# scematic.net
KiCad netlist of a schematic drawn in Altium Designer
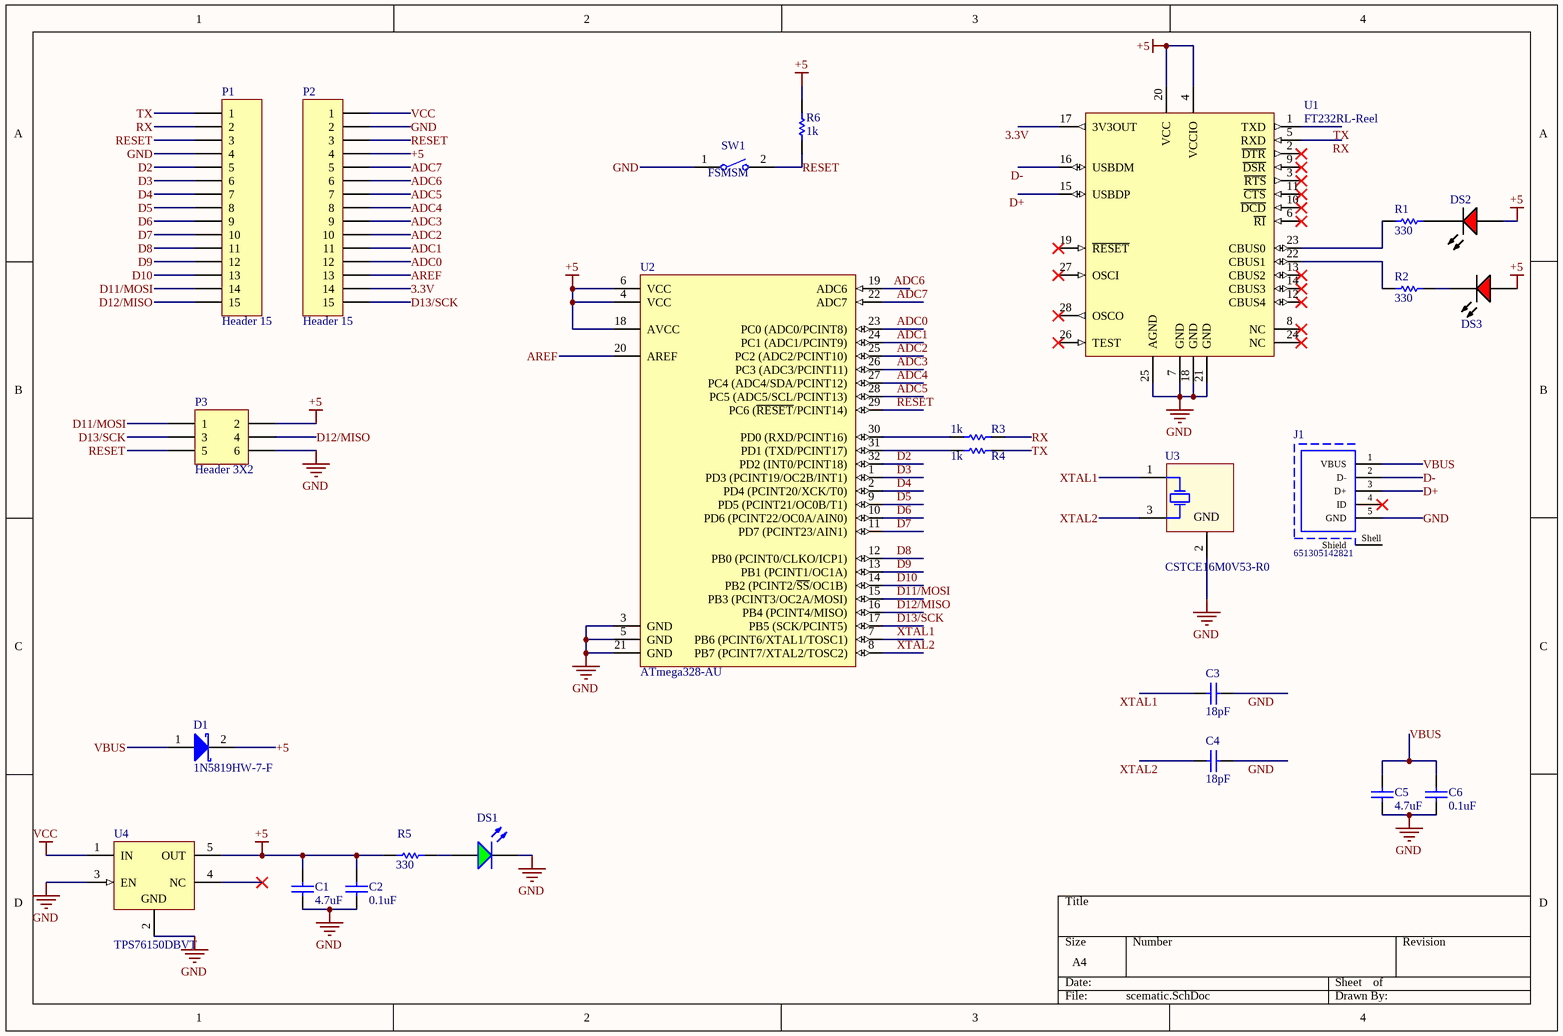
[diagram p0: scematic.SchDoc]

(export (version "E")
  (design (tool "Eeschema 10.0.6"))
  (components
    (comp (ref "C1")
      (value "4.7uF")
      (footprint "CAPC1005X55X25NL05T10")
      (fields (field (name "PART NUMBER") "GRM155R60J475ME47D") (field (name "MANUFACTURER") "Murata"))
      (libsource (lib "Altium Content Vault") (part "CAP"))
    )
    (comp (ref "C2")
      (value "0.1uF")
      (footprint "CAPC1005X55X25ML05T10")
      (description "Chip Capacitor, 0.1 uF, +/- 10%, 16 V, -55 to 125 degC, 0402 (1005 Metric), RoHS, Tape and Reel")
      (fields (field (name "VOLTAGE") "16V") (field (name "TOLERANCE") "10%"))
      (libsource (lib "Altium Content Vault") (part "CAP-NP-2"))
    )
    (comp (ref "C3")
      (value "18pF")
      (footprint "CAPC1005X55X30LL05T10")
      (fields (field (name "PART NUMBER") "C0402C180J5GACTU") (field (name "MANUFACTURER") "Kemet"))
      (libsource (lib "Altium Content Vault") (part "CAP"))
    )
    (comp (ref "C4")
      (value "18pF")
      (footprint "CAPC1005X55X30LL05T10")
      (fields (field (name "PART NUMBER") "C0402C180J5GACTU") (field (name "MANUFACTURER") "Kemet"))
      (libsource (lib "Altium Content Vault") (part "CAP"))
    )
    (comp (ref "C5")
      (value "4.7uF")
      (footprint "CAPC1005X55X25NL05T10")
      (fields (field (name "PART NUMBER") "GRM155R60J475ME47D") (field (name "MANUFACTURER") "Murata"))
      (libsource (lib "Altium Content Vault") (part "CAP"))
    )
    (comp (ref "C6")
      (value "0.1uF")
      (footprint "CAPC1005X55X25ML05T10")
      (description "Chip Capacitor, 0.1 uF, +/- 10%, 16 V, -55 to 125 degC, 0402 (1005 Metric), RoHS, Tape and Reel")
      (fields (field (name "VOLTAGE") "16V") (field (name "TOLERANCE") "10%"))
      (libsource (lib "Altium Content Vault") (part "CAP-NP-2"))
    )
    (comp (ref "D1")
      (value "1N5819HW-7-F")
      (footprint "DIOD-SOD-123-2_V")
      (fields (field (name "MANUFACTURER") "Diodes Inc"))
      (libsource (lib "Altium Content Vault") (part "DIOD-DSKY-A1K2-2"))
    )
    (comp (ref "DS1")
      (value "APT1608SGC")
      (footprint "KING-APT1608SGC_V")
      (description "Super Bright Green LED, 62.5 mW, 25 mA, -40 to 85 degC, 2-Pin SMD, RoHS, Tape and Reel")
      (fields (field (name "MANUFACTURER") "Kingbright"))
      (libsource (lib "Altium Content Vault") (part "LED-GREEN-AK-2"))
    )
    (comp (ref "DS2")
      (value "TLMS1000-GS08")
      (footprint "VISH-TLMS1000_V")
      (description "Low Current LED, 40 mW, 1.8 V, -40 to 100 degC, 2-Pin SMD (0603), RoHS, Tape and Reel")
      (fields (field (name "MANUFACTURER") "Vishay"))
      (libsource (lib "Altium Content Vault") (part "LED-RED-AK-2"))
    )
    (comp (ref "DS3")
      (value "TLMS1000-GS08")
      (footprint "VISH-TLMS1000_V")
      (description "Low Current LED, 40 mW, 1.8 V, -40 to 100 degC, 2-Pin SMD (0603), RoHS, Tape and Reel")
      (fields (field (name "MANUFACTURER") "Vishay"))
      (libsource (lib "Altium Content Vault") (part "LED-RED-AK-2"))
    )
    (comp (ref "J1")
      (value "651305142821")
      (footprint "651305142821")
      (description "Mini USB 2.0 Type AB Receptacle WR-COM, Horizontal, SMT, with Pads")
      (fields (field (name "MANUFACTURER") "Wurth Elektronik") (field (name "PUBLISHER") "WurthElektronik"))
      (libsource (lib "Altium Content Vault") (part "WE-USB-5-1SHLD"))
    )
    (comp (ref "P1")
      (value "Header 15")
      (footprint "HDR1X15")
      (description "Header, 15-Pin")
      (fields (field (name "PUBLISHER") "Altium Limited"))
      (libsource (lib "") (part "Header 15_1"))
    )
    (comp (ref "P2")
      (value "Header 15")
      (footprint "HDR1X15")
      (description "Header, 15-Pin")
      (fields (field (name "PUBLISHER") "Altium Limited"))
      (libsource (lib "Miscellaneous Connectors") (part "Header 15"))
    )
    (comp (ref "P3")
      (value "Header 3X2")
      (footprint "HDR2X3")
      (description "Header, 3-Pin, Dual row")
      (fields (field (name "PUBLISHER") "Altium Limited"))
      (libsource (lib "Miscellaneous Connectors") (part "Header 3X2"))
    )
    (comp (ref "R1")
      (value "330")
      (footprint "RESC1608X55X30ML15T15")
      (fields (field (name "PART NUMBER") "ERJ-3GEYJ331V") (field (name "MANUFACTURER") "Panasonic"))
      (libsource (lib "Altium Content Vault") (part "RES"))
    )
    (comp (ref "R2")
      (value "330")
      (footprint "RESC1608X55X30ML15T15")
      (fields (field (name "PART NUMBER") "ERJ-3GEYJ331V") (field (name "MANUFACTURER") "Panasonic"))
      (libsource (lib "Altium Content Vault") (part "RES"))
    )
    (comp (ref "R3")
      (value "1k")
      (footprint "RESC1608X55X30ML15T15")
      (fields (field (name "PART NUMBER") "ERJ-3GEYJ331V") (field (name "MANUFACTURER") "Panasonic"))
      (libsource (lib "Altium Content Vault") (part "RES"))
    )
    (comp (ref "R4")
      (value "1k")
      (footprint "RESC1608X55X30ML15T15")
      (fields (field (name "PART NUMBER") "ERJ-3GEYJ331V") (field (name "MANUFACTURER") "Panasonic"))
      (libsource (lib "Altium Content Vault") (part "RES"))
    )
    (comp (ref "R5")
      (value "330")
      (footprint "RESC1608X55X30ML15T15")
      (fields (field (name "PART NUMBER") "ERJ-3GEYJ331V") (field (name "MANUFACTURER") "Panasonic"))
      (libsource (lib "Altium Content Vault") (part "RES"))
    )
    (comp (ref "R6")
      (value "1k")
      (footprint "RESC1608X55X30ML15T15")
      (fields (field (name "PART NUMBER") "ERJ-3GEYJ331V") (field (name "MANUFACTURER") "Panasonic"))
      (libsource (lib "Altium Content Vault") (part "RES"))
    )
    (comp (ref "SW1")
      (value "FSMSM")
      (footprint "TECO-FSMSM-2_V")
      (description "FSMSM Push Button Switch, 50 mA, -35 to 85 degC, 2-Pin SMD, RoHS, Bulk")
      (fields (field (name "MANUFACTURER") "TE Connectivity"))
      (libsource (lib "Altium Content Vault") (part "SW-SPST-2_C"))
    )
    (comp (ref "U1")
      (value "FT232RL-Reel")
      (footprint "SSOP-28_L")
      (description "USB UART Asynchronous Serial Data Transfer Chip, 28-pin SSOP, Tape and Reel")
      (fields (field (name "MANUFACTURER") "FTDI"))
      (libsource (lib "Altium Content Vault") (part "COM-UART-FT232R-IL28"))
    )
    (comp (ref "U2")
      (value "ATmega328-AU")
      (footprint "32A_L")
      (libsource (lib "Altium Content Vault") (part "MC-8B-ATM48-SQ32"))
    )
    (comp (ref "U3")
      (value "CSTCE16M0V53-R0")
      (footprint "MURA-CSTCE_V-3_V")
      (fields (field (name "MANUFACTURER") "Murata"))
      (libsource (lib "Altium Content Vault") (part "MURA-CSTCE_V-3"))
    )
    (comp (ref "U4")
      (value "TPS76150DBVT")
      (footprint "DBV0005A_N")
      (fields (field (name "MANUFACTURER") "Texas Instruments"))
      (libsource (lib "Altium Content Vault") (part "TI-TXX7XXXX-5"))
    )
  )
  (nets
    (net (code "1") (name "+5") (class "Default")
      (node (ref "C1") (pin "2") (pinfunction "2_2") (pintype "passive"))
      (node (ref "C2") (pin "2") (pinfunction "2_2") (pintype "passive"))
      (node (ref "D1") (pin "2") (pinfunction "K_2") (pintype "passive"))
      (node (ref "DS2") (pin "1") (pinfunction "A_1") (pintype "passive"))
      (node (ref "DS3") (pin "1") (pinfunction "A_1") (pintype "passive"))
      (node (ref "P2") (pin "4") (pinfunction "4_4") (pintype "passive"))
      (node (ref "P3") (pin "2") (pinfunction "2_2") (pintype "passive"))
      (node (ref "R5") (pin "1") (pinfunction "1_1") (pintype "passive"))
      (node (ref "R6") (pin "2") (pinfunction "2_2") (pintype "passive"))
      (node (ref "U1") (pin "20") (pinfunction "VCC_20") (pintype "power_in"))
      (node (ref "U1") (pin "4") (pinfunction "VCCIO_4") (pintype "power_in"))
      (node (ref "U2") (pin "18") (pinfunction "AVCC_18") (pintype "power_in"))
      (node (ref "U2") (pin "4") (pinfunction "VCC_4") (pintype "power_in"))
      (node (ref "U2") (pin "6") (pinfunction "VCC_6") (pintype "power_in"))
      (node (ref "U4") (pin "5") (pinfunction "OUT_5") (pintype "power_in"))
    )
    (net (code "2") (name "/3.3V") (class "Default")
      (node (ref "P2") (pin "14") (pinfunction "14_14") (pintype "passive"))
      (node (ref "U1") (pin "17") (pinfunction "3V3OUT_17") (pintype "output"))
    )
    (net (code "3") (name "/ADC0") (class "Default")
      (node (ref "P2") (pin "12") (pinfunction "12_12") (pintype "passive"))
      (node (ref "U2") (pin "23") (pinfunction "PC0_(ADC0/PCINT8)_23") (pintype "bidirectional"))
    )
    (net (code "4") (name "/ADC1") (class "Default")
      (node (ref "P2") (pin "11") (pinfunction "11_11") (pintype "passive"))
      (node (ref "U2") (pin "24") (pinfunction "PC1_(ADC1/PCINT9)_24") (pintype "bidirectional"))
    )
    (net (code "5") (name "/ADC2") (class "Default")
      (node (ref "P2") (pin "10") (pinfunction "10_10") (pintype "passive"))
      (node (ref "U2") (pin "25") (pinfunction "PC2_(ADC2/PCINT10)_25") (pintype "bidirectional"))
    )
    (net (code "6") (name "/ADC3") (class "Default")
      (node (ref "P2") (pin "9") (pinfunction "9_9") (pintype "passive"))
      (node (ref "U2") (pin "26") (pinfunction "PC3_(ADC3/PCINT11)_26") (pintype "bidirectional"))
    )
    (net (code "7") (name "/ADC4") (class "Default")
      (node (ref "P2") (pin "8") (pinfunction "8_8") (pintype "passive"))
      (node (ref "U2") (pin "27") (pinfunction "PC4_(ADC4/SDA/PCINT12)_27") (pintype "bidirectional"))
    )
    (net (code "8") (name "/ADC5") (class "Default")
      (node (ref "P2") (pin "7") (pinfunction "7_7") (pintype "passive"))
      (node (ref "U2") (pin "28") (pinfunction "PC5_(ADC5/SCL/PCINT13)_28") (pintype "bidirectional"))
    )
    (net (code "9") (name "/ADC6") (class "Default")
      (node (ref "P2") (pin "6") (pinfunction "6_6") (pintype "passive"))
      (node (ref "U2") (pin "19") (pinfunction "ADC6_19") (pintype "input"))
    )
    (net (code "10") (name "/ADC7") (class "Default")
      (node (ref "P2") (pin "5") (pinfunction "5_5") (pintype "passive"))
      (node (ref "U2") (pin "22") (pinfunction "ADC7_22") (pintype "input"))
    )
    (net (code "11") (name "/AREF") (class "Default")
      (node (ref "P2") (pin "13") (pinfunction "13_13") (pintype "passive"))
      (node (ref "U2") (pin "20") (pinfunction "AREF_20") (pintype "passive"))
    )
    (net (code "12") (name "/D+") (class "Default")
      (node (ref "J1") (pin "3") (pinfunction "D+_3") (pintype "passive"))
      (node (ref "U1") (pin "15") (pinfunction "USBDP_15") (pintype "bidirectional"))
    )
    (net (code "13") (name "/D-") (class "Default")
      (node (ref "J1") (pin "2") (pinfunction "D-_2") (pintype "passive"))
      (node (ref "U1") (pin "16") (pinfunction "USBDM_16") (pintype "bidirectional"))
    )
    (net (code "14") (name "/D2") (class "Default")
      (node (ref "P1") (pin "5") (pinfunction "5_5") (pintype "passive"))
      (node (ref "U2") (pin "32") (pinfunction "PD2_(INT0/PCINT18)_32") (pintype "bidirectional"))
    )
    (net (code "15") (name "/D3") (class "Default")
      (node (ref "P1") (pin "6") (pinfunction "6_6") (pintype "passive"))
      (node (ref "U2") (pin "1") (pinfunction "PD3_(PCINT19/OC2B/INT1)_1") (pintype "bidirectional"))
    )
    (net (code "16") (name "/D4") (class "Default")
      (node (ref "P1") (pin "7") (pinfunction "7_7") (pintype "passive"))
      (node (ref "U2") (pin "2") (pinfunction "PD4_(PCINT20/XCK/T0)_2") (pintype "bidirectional"))
    )
    (net (code "17") (name "/D5") (class "Default")
      (node (ref "P1") (pin "8") (pinfunction "8_8") (pintype "passive"))
      (node (ref "U2") (pin "9") (pinfunction "PD5_(PCINT21/OC0B/T1)_9") (pintype "bidirectional"))
    )
    (net (code "18") (name "/D6") (class "Default")
      (node (ref "P1") (pin "9") (pinfunction "9_9") (pintype "passive"))
      (node (ref "U2") (pin "10") (pinfunction "PD6_(PCINT22/OC0A/AIN0)_10") (pintype "bidirectional"))
    )
    (net (code "19") (name "/D7") (class "Default")
      (node (ref "P1") (pin "10") (pinfunction "10_10") (pintype "passive"))
      (node (ref "U2") (pin "11") (pinfunction "PD7_(PCINT23/AIN1)_11") (pintype "bidirectional"))
    )
    (net (code "20") (name "/D8") (class "Default")
      (node (ref "P1") (pin "11") (pinfunction "11_11") (pintype "passive"))
      (node (ref "U2") (pin "12") (pinfunction "PB0_(PCINT0/CLKO/ICP1)_12") (pintype "bidirectional"))
    )
    (net (code "21") (name "/D9") (class "Default")
      (node (ref "P1") (pin "12") (pinfunction "12_12") (pintype "passive"))
      (node (ref "U2") (pin "13") (pinfunction "PB1_(PCINT1/OC1A)_13") (pintype "bidirectional"))
    )
    (net (code "22") (name "/D10") (class "Default")
      (node (ref "P1") (pin "13") (pinfunction "13_13") (pintype "passive"))
      (node (ref "U2") (pin "14") (pinfunction "PB2_(PCINT2/~{SS}/OC1B)_14") (pintype "bidirectional"))
    )
    (net (code "23") (name "/D11{slash}MOSI") (class "Default")
      (node (ref "P1") (pin "14") (pinfunction "14_14") (pintype "passive"))
      (node (ref "P3") (pin "1") (pinfunction "1_1") (pintype "passive"))
      (node (ref "U2") (pin "15") (pinfunction "PB3_(PCINT3/OC2A/MOSI)_15") (pintype "bidirectional"))
    )
    (net (code "24") (name "/D12{slash}MISO") (class "Default")
      (node (ref "P1") (pin "15") (pinfunction "15_15") (pintype "passive"))
      (node (ref "P3") (pin "4") (pinfunction "4_4") (pintype "passive"))
      (node (ref "U2") (pin "16") (pinfunction "PB4_(PCINT4/MISO)_16") (pintype "bidirectional"))
    )
    (net (code "25") (name "/D13{slash}SCK") (class "Default")
      (node (ref "P2") (pin "15") (pinfunction "15_15") (pintype "passive"))
      (node (ref "P3") (pin "3") (pinfunction "3_3") (pintype "passive"))
      (node (ref "U2") (pin "17") (pinfunction "PB5_(SCK/PCINT5)_17") (pintype "bidirectional"))
    )
    (net (code "26") (name "/RESET") (class "Default")
      (node (ref "P1") (pin "3") (pinfunction "3_3") (pintype "passive"))
      (node (ref "P2") (pin "3") (pinfunction "3_3") (pintype "passive"))
      (node (ref "P3") (pin "5") (pinfunction "5_5") (pintype "passive"))
      (node (ref "R6") (pin "1") (pinfunction "1_1") (pintype "passive"))
      (node (ref "SW1") (pin "2") (pinfunction "2_2") (pintype "passive"))
      (node (ref "U2") (pin "29") (pinfunction "PC6_(~{RESET}/PCINT14)_29") (pintype "bidirectional"))
    )
    (net (code "27") (name "/RX") (class "Default")
      (node (ref "P1") (pin "2") (pinfunction "2_2") (pintype "passive"))
      (node (ref "R3") (pin "2") (pinfunction "2_2") (pintype "passive"))
      (node (ref "U1") (pin "5") (pinfunction "RXD_5") (pintype "input"))
    )
    (net (code "28") (name "/TX") (class "Default")
      (node (ref "P1") (pin "1") (pinfunction "1_1") (pintype "passive"))
      (node (ref "R4") (pin "2") (pinfunction "2_2") (pintype "passive"))
      (node (ref "U1") (pin "1") (pinfunction "TXD_1") (pintype "output"))
    )
    (net (code "29") (name "/VBUS") (class "Default")
      (node (ref "C5") (pin "2") (pinfunction "2_2") (pintype "passive"))
      (node (ref "C6") (pin "2") (pinfunction "2_2") (pintype "passive"))
      (node (ref "D1") (pin "1") (pinfunction "A_1") (pintype "passive"))
      (node (ref "J1") (pin "1") (pinfunction "VBUS_1") (pintype "passive"))
    )
    (net (code "30") (name "/XTAL1") (class "Default")
      (node (ref "C3") (pin "1") (pinfunction "1_1") (pintype "passive"))
      (node (ref "U2") (pin "7") (pinfunction "PB6_(PCINT6/XTAL1/TOSC1)_7") (pintype "bidirectional"))
      (node (ref "U3") (pin "1") (pinfunction "C1_1") (pintype "passive"))
    )
    (net (code "31") (name "/XTAL2") (class "Default")
      (node (ref "C4") (pin "1") (pinfunction "1_1") (pintype "passive"))
      (node (ref "U2") (pin "8") (pinfunction "PB7_(PCINT7/XTAL2/TOSC2)_8") (pintype "bidirectional"))
      (node (ref "U3") (pin "3") (pinfunction "C2_3") (pintype "passive"))
    )
    (net (code "32") (name "GND") (class "Default")
      (node (ref "C1") (pin "1") (pinfunction "1_1") (pintype "passive"))
      (node (ref "C2") (pin "1") (pinfunction "1_1") (pintype "passive"))
      (node (ref "C3") (pin "2") (pinfunction "2_2") (pintype "passive"))
      (node (ref "C4") (pin "2") (pinfunction "2_2") (pintype "passive"))
      (node (ref "C5") (pin "1") (pinfunction "1_1") (pintype "passive"))
      (node (ref "C6") (pin "1") (pinfunction "1_1") (pintype "passive"))
      (node (ref "DS1") (pin "2") (pinfunction "K_2") (pintype "passive"))
      (node (ref "J1") (pin "5") (pinfunction "GND_5") (pintype "passive"))
      (node (ref "P1") (pin "4") (pinfunction "4_4") (pintype "passive"))
      (node (ref "P2") (pin "2") (pinfunction "2_2") (pintype "passive"))
      (node (ref "P3") (pin "6") (pinfunction "6_6") (pintype "passive"))
      (node (ref "SW1") (pin "1") (pinfunction "1_1") (pintype "passive"))
      (node (ref "U1") (pin "18") (pinfunction "GND_18") (pintype "power_in"))
      (node (ref "U1") (pin "21") (pinfunction "GND_21") (pintype "power_in"))
      (node (ref "U1") (pin "25") (pinfunction "AGND_25") (pintype "power_in"))
      (node (ref "U1") (pin "7") (pinfunction "GND_7") (pintype "power_in"))
      (node (ref "U2") (pin "21") (pinfunction "GND_21") (pintype "power_in"))
      (node (ref "U2") (pin "3") (pinfunction "GND_3") (pintype "power_in"))
      (node (ref "U2") (pin "5") (pinfunction "GND_5") (pintype "power_in"))
      (node (ref "U3") (pin "2") (pinfunction "GND_2") (pintype "power_in"))
      (node (ref "U4") (pin "2") (pinfunction "GND_2") (pintype "power_in"))
      (node (ref "U4") (pin "3") (pinfunction "EN_3") (pintype "input"))
    )
    (net (code "33") (name "Net-(DS1-A)") (class "Default")
      (node (ref "DS1") (pin "1") (pinfunction "A_1") (pintype "passive"))
      (node (ref "R5") (pin "2") (pinfunction "2_2") (pintype "passive"))
    )
    (net (code "34") (name "Net-(DS2-K)") (class "Default")
      (node (ref "DS2") (pin "2") (pinfunction "K_2") (pintype "passive"))
      (node (ref "R1") (pin "2") (pinfunction "2_2") (pintype "passive"))
    )
    (net (code "35") (name "Net-(DS3-K)") (class "Default")
      (node (ref "DS3") (pin "2") (pinfunction "K_2") (pintype "passive"))
      (node (ref "R2") (pin "2") (pinfunction "2_2") (pintype "passive"))
    )
    (net (code "36") (name "Net-(U1-CBUS0)") (class "Default")
      (node (ref "R1") (pin "1") (pinfunction "1_1") (pintype "passive"))
      (node (ref "U1") (pin "23") (pinfunction "CBUS0_23") (pintype "bidirectional"))
    )
    (net (code "37") (name "Net-(U1-CBUS1)") (class "Default")
      (node (ref "R2") (pin "1") (pinfunction "1_1") (pintype "passive"))
      (node (ref "U1") (pin "22") (pinfunction "CBUS1_22") (pintype "bidirectional"))
    )
    (net (code "38") (name "Net-(U2-PD0_(RXD{slash}PCINT16))") (class "Default")
      (node (ref "R3") (pin "1") (pinfunction "1_1") (pintype "passive"))
      (node (ref "U2") (pin "30") (pinfunction "PD0_(RXD/PCINT16)_30") (pintype "bidirectional"))
    )
    (net (code "39") (name "Net-(U2-PD1_(TXD{slash}PCINT17))") (class "Default")
      (node (ref "R4") (pin "1") (pinfunction "1_1") (pintype "passive"))
      (node (ref "U2") (pin "31") (pinfunction "PD1_(TXD/PCINT17)_31") (pintype "bidirectional"))
    )
    (net (code "40") (name "VCC") (class "Default")
      (node (ref "P2") (pin "1") (pinfunction "1_1") (pintype "passive"))
      (node (ref "U4") (pin "1") (pinfunction "IN_1") (pintype "power_in"))
    )
    (net (code "41") (name "unconnected-(J1-ID-Pad4)") (class "Default")
      (node (ref "J1") (pin "4") (pinfunction "ID_4") (pintype "passive+no_connect"))
    )
    (net (code "42") (name "unconnected-(J1-Shield-PadShell)") (class "Default")
      (node (ref "J1") (pin "Shell") (pinfunction "Shield_Shell") (pintype "passive"))
    )
    (net (code "43") (name "unconnected-(U1-CBUS2-Pad13)") (class "Default")
      (node (ref "U1") (pin "13") (pinfunction "CBUS2_13") (pintype "bidirectional+no_connect"))
    )
    (net (code "44") (name "unconnected-(U1-CBUS3-Pad14)") (class "Default")
      (node (ref "U1") (pin "14") (pinfunction "CBUS3_14") (pintype "bidirectional+no_connect"))
    )
    (net (code "45") (name "unconnected-(U1-CBUS4-Pad12)") (class "Default")
      (node (ref "U1") (pin "12") (pinfunction "CBUS4_12") (pintype "bidirectional+no_connect"))
    )
    (net (code "46") (name "unconnected-(U1-NC-Pad8)") (class "Default")
      (node (ref "U1") (pin "8") (pinfunction "NC_8") (pintype "passive+no_connect"))
    )
    (net (code "47") (name "unconnected-(U1-NC-Pad24)") (class "Default")
      (node (ref "U1") (pin "24") (pinfunction "NC_24") (pintype "passive+no_connect"))
    )
    (net (code "48") (name "unconnected-(U1-OSCI-Pad27)") (class "Default")
      (node (ref "U1") (pin "27") (pinfunction "OSCI_27") (pintype "input+no_connect"))
    )
    (net (code "49") (name "unconnected-(U1-OSCO-Pad28)") (class "Default")
      (node (ref "U1") (pin "28") (pinfunction "OSCO_28") (pintype "output+no_connect"))
    )
    (net (code "50") (name "unconnected-(U1-TEST-Pad26)") (class "Default")
      (node (ref "U1") (pin "26") (pinfunction "TEST_26") (pintype "input+no_connect"))
    )
    (net (code "51") (name "unconnected-(U1-~{CTS}-Pad11)") (class "Default")
      (node (ref "U1") (pin "11") (pinfunction "~{CTS}_11") (pintype "input+no_connect"))
    )
    (net (code "52") (name "unconnected-(U1-~{DCD}-Pad10)") (class "Default")
      (node (ref "U1") (pin "10") (pinfunction "~{DCD}_10") (pintype "input+no_connect"))
    )
    (net (code "53") (name "unconnected-(U1-~{DSR}-Pad9)") (class "Default")
      (node (ref "U1") (pin "9") (pinfunction "~{DSR}_9") (pintype "input+no_connect"))
    )
    (net (code "54") (name "unconnected-(U1-~{DTR}-Pad2)") (class "Default")
      (node (ref "U1") (pin "2") (pinfunction "~{DTR}_2") (pintype "output+no_connect"))
    )
    (net (code "55") (name "unconnected-(U1-~{RESET}-Pad19)") (class "Default")
      (node (ref "U1") (pin "19") (pinfunction "~{RESET}_19") (pintype "input+no_connect"))
    )
    (net (code "56") (name "unconnected-(U1-~{RI}-Pad6)") (class "Default")
      (node (ref "U1") (pin "6") (pinfunction "~{RI}_6") (pintype "input+no_connect"))
    )
    (net (code "57") (name "unconnected-(U1-~{RTS}-Pad3)") (class "Default")
      (node (ref "U1") (pin "3") (pinfunction "~{RTS}_3") (pintype "output+no_connect"))
    )
    (net (code "58") (name "unconnected-(U4-NC-Pad4)") (class "Default")
      (node (ref "U4") (pin "4") (pinfunction "NC_4") (pintype "passive+no_connect"))
    )
  )
)
